# USB.net
KiCad netlist of a schematic drawn in Altium Designer
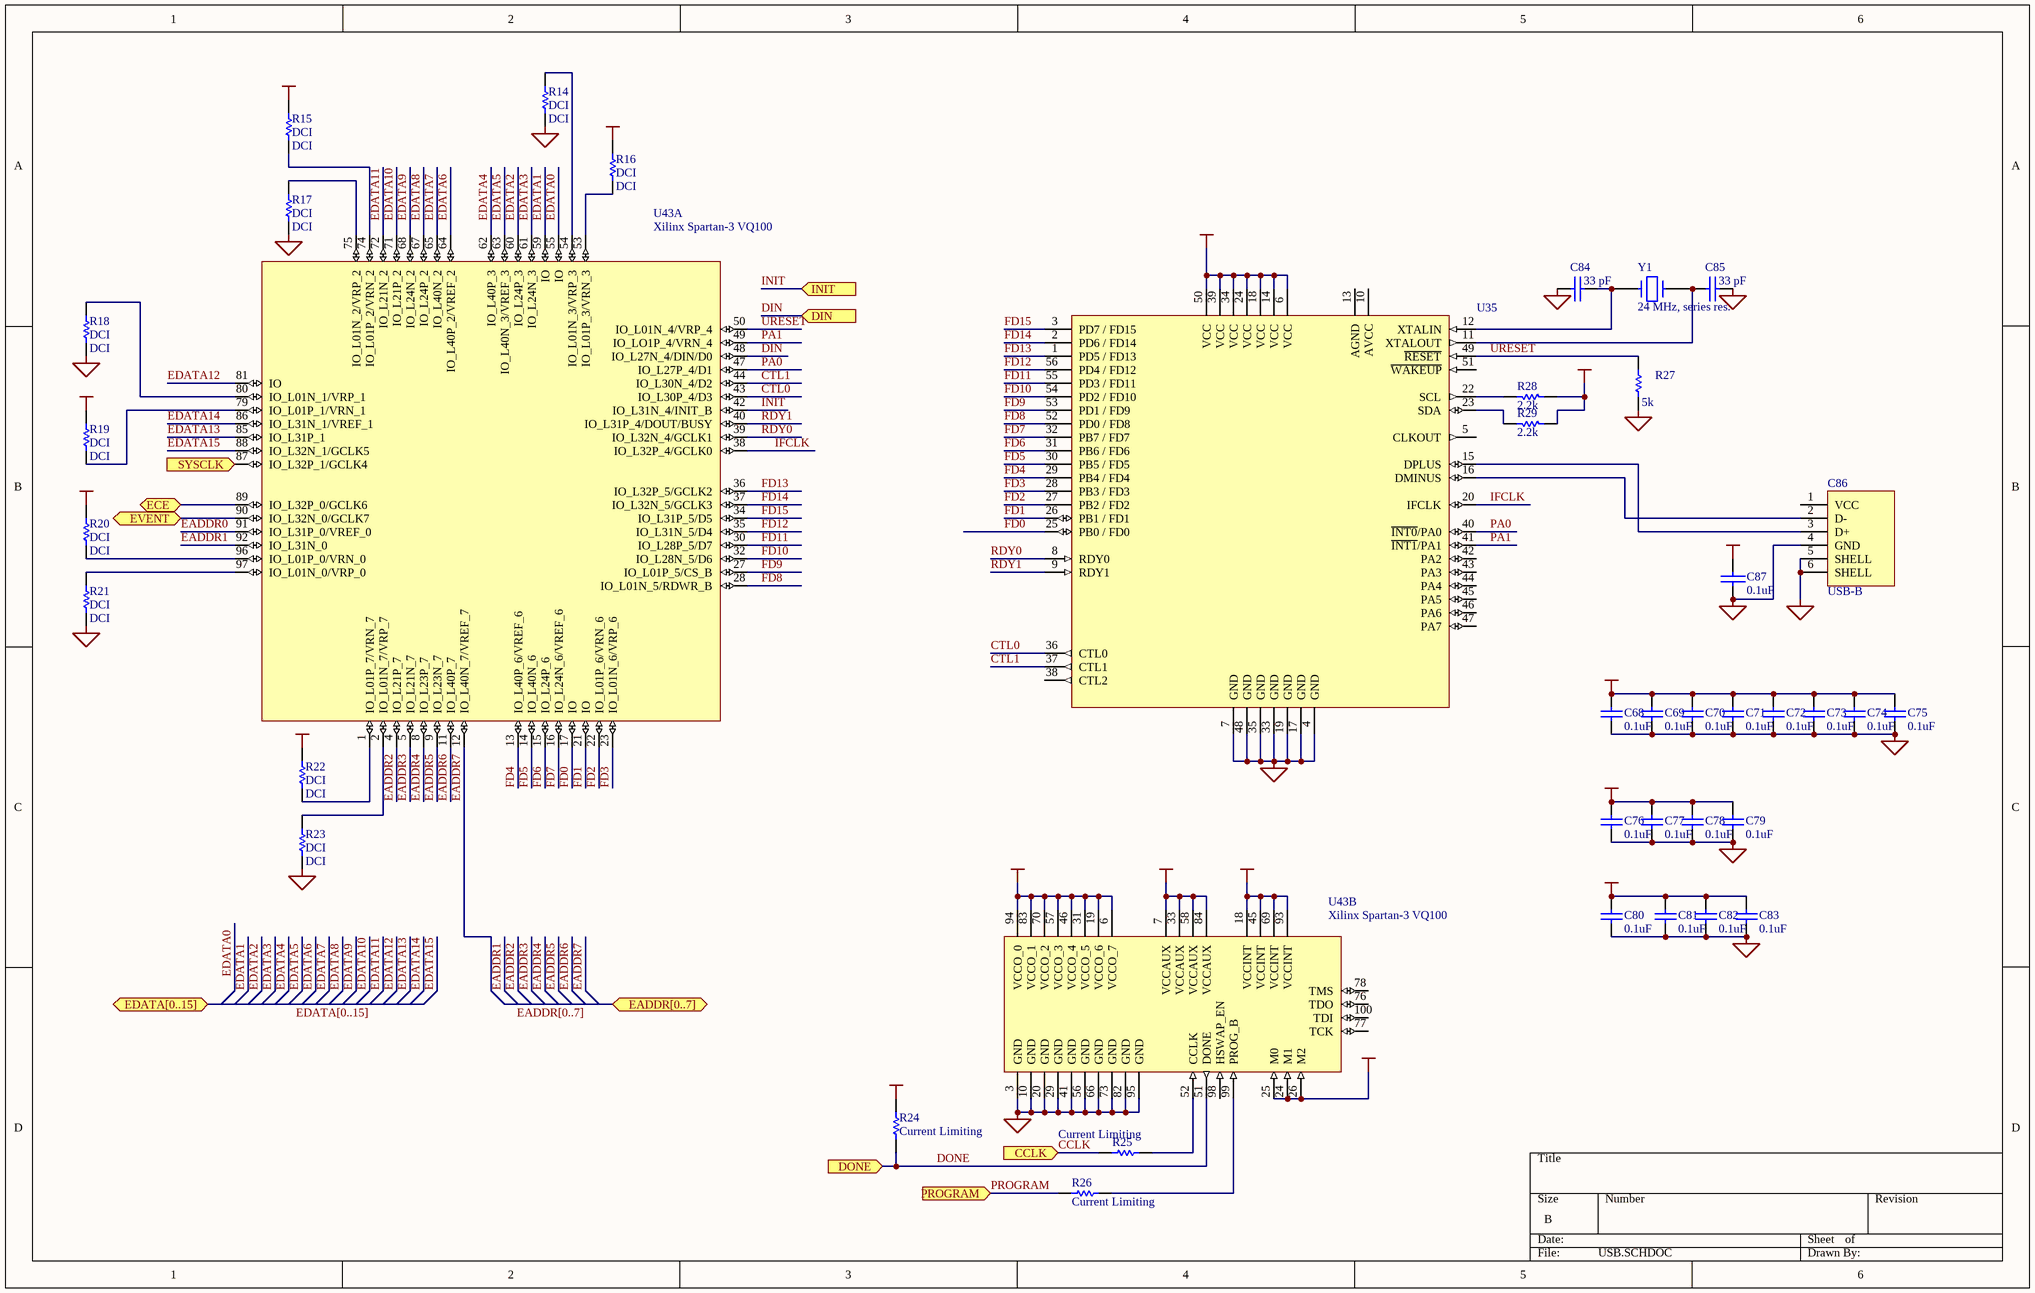
[diagram p0: USB.SCHDOC]

(export (version "E")
  (design (tool "Eeschema 10.0.6"))
  (components
    (comp (ref "C68")
      (value "Cap")
      (footprint "CC1608-0603")
      (description "Capacitor")
      (fields
        (field (name "MANUFACTURER") "Generic Components")
        (field (name "ALTIUM_VALUE") "0.1uF")
        (field (name "PUBLISHER") "Altium Limited")
      )
      (libsource (lib "Miscellaneous Devices") (part "Cap"))
    )
    (comp (ref "C69")
      (value "Cap")
      (footprint "CC1608-0603")
      (description "Capacitor")
      (fields
        (field (name "MANUFACTURER") "Generic Components")
        (field (name "ALTIUM_VALUE") "0.1uF")
        (field (name "PUBLISHER") "Altium Limited")
      )
      (libsource (lib "Miscellaneous Devices") (part "Cap"))
    )
    (comp (ref "C70")
      (value "Cap")
      (footprint "CC1608-0603")
      (description "Capacitor")
      (fields
        (field (name "MANUFACTURER") "Generic Components")
        (field (name "ALTIUM_VALUE") "0.1uF")
        (field (name "PUBLISHER") "Altium Limited")
      )
      (libsource (lib "Miscellaneous Devices") (part "Cap"))
    )
    (comp (ref "C71")
      (value "Cap")
      (footprint "CC1608-0603")
      (description "Capacitor")
      (fields
        (field (name "MANUFACTURER") "Generic Components")
        (field (name "ALTIUM_VALUE") "0.1uF")
        (field (name "PUBLISHER") "Altium Limited")
      )
      (libsource (lib "Miscellaneous Devices") (part "Cap"))
    )
    (comp (ref "C72")
      (value "Cap")
      (footprint "CC1608-0603")
      (description "Capacitor")
      (fields
        (field (name "MANUFACTURER") "Generic Components")
        (field (name "ALTIUM_VALUE") "0.1uF")
        (field (name "PUBLISHER") "Altium Limited")
      )
      (libsource (lib "Miscellaneous Devices") (part "Cap"))
    )
    (comp (ref "C73")
      (value "Cap")
      (footprint "CC1608-0603")
      (description "Capacitor")
      (fields
        (field (name "MANUFACTURER") "Generic Components")
        (field (name "ALTIUM_VALUE") "0.1uF")
        (field (name "PUBLISHER") "Altium Limited")
      )
      (libsource (lib "Miscellaneous Devices") (part "Cap"))
    )
    (comp (ref "C74")
      (value "Cap")
      (footprint "CC1608-0603")
      (description "Capacitor")
      (fields
        (field (name "MANUFACTURER") "Generic Components")
        (field (name "ALTIUM_VALUE") "0.1uF")
        (field (name "PUBLISHER") "Altium Limited")
      )
      (libsource (lib "Miscellaneous Devices") (part "Cap"))
    )
    (comp (ref "C75")
      (value "Cap")
      (footprint "CC1608-0603")
      (description "Capacitor")
      (fields
        (field (name "MANUFACTURER") "Generic Components")
        (field (name "ALTIUM_VALUE") "0.1uF")
        (field (name "PUBLISHER") "Altium Limited")
      )
      (libsource (lib "Miscellaneous Devices") (part "Cap"))
    )
    (comp (ref "C76")
      (value "Cap")
      (footprint "CC1608-0603")
      (description "Capacitor")
      (fields
        (field (name "MANUFACTURER") "Generic Components")
        (field (name "ALTIUM_VALUE") "0.1uF")
        (field (name "PUBLISHER") "Altium Limited")
      )
      (libsource (lib "Miscellaneous Devices") (part "Cap"))
    )
    (comp (ref "C77")
      (value "Cap")
      (footprint "CC1608-0603")
      (description "Capacitor")
      (fields
        (field (name "MANUFACTURER") "Generic Components")
        (field (name "ALTIUM_VALUE") "0.1uF")
        (field (name "PUBLISHER") "Altium Limited")
      )
      (libsource (lib "Miscellaneous Devices") (part "Cap"))
    )
    (comp (ref "C78")
      (value "Cap")
      (footprint "CC1608-0603")
      (description "Capacitor")
      (fields
        (field (name "MANUFACTURER") "Generic Components")
        (field (name "ALTIUM_VALUE") "0.1uF")
        (field (name "PUBLISHER") "Altium Limited")
      )
      (libsource (lib "Miscellaneous Devices") (part "Cap"))
    )
    (comp (ref "C79")
      (value "Cap")
      (footprint "CC1608-0603")
      (description "Capacitor")
      (fields
        (field (name "MANUFACTURER") "Generic Components")
        (field (name "ALTIUM_VALUE") "0.1uF")
        (field (name "PUBLISHER") "Altium Limited")
      )
      (libsource (lib "Miscellaneous Devices") (part "Cap"))
    )
    (comp (ref "C80")
      (value "Cap")
      (footprint "CC1608-0603")
      (description "Capacitor")
      (fields
        (field (name "MANUFACTURER") "Generic Components")
        (field (name "ALTIUM_VALUE") "0.1uF")
        (field (name "PUBLISHER") "Altium Limited")
      )
      (libsource (lib "Miscellaneous Devices") (part "Cap"))
    )
    (comp (ref "C81")
      (value "Cap")
      (footprint "CC1608-0603")
      (description "Capacitor")
      (fields
        (field (name "MANUFACTURER") "Generic Components")
        (field (name "ALTIUM_VALUE") "0.1uF")
        (field (name "PUBLISHER") "Altium Limited")
      )
      (libsource (lib "Miscellaneous Devices") (part "Cap"))
    )
    (comp (ref "C82")
      (value "Cap")
      (footprint "CC1608-0603")
      (description "Capacitor")
      (fields
        (field (name "MANUFACTURER") "Generic Components")
        (field (name "ALTIUM_VALUE") "0.1uF")
        (field (name "PUBLISHER") "Altium Limited")
      )
      (libsource (lib "Miscellaneous Devices") (part "Cap"))
    )
    (comp (ref "C83")
      (value "Cap")
      (footprint "CC1608-0603")
      (description "Capacitor")
      (fields
        (field (name "MANUFACTURER") "Generic Components")
        (field (name "ALTIUM_VALUE") "0.1uF")
        (field (name "PUBLISHER") "Altium Limited")
      )
      (libsource (lib "Miscellaneous Devices") (part "Cap"))
    )
    (comp (ref "C84")
      (value "33 pF")
      (footprint "CC1608-0603")
      (description "Capacitor")
      (libsource (lib "*") (part "CAP"))
    )
    (comp (ref "C85")
      (value "33 pF")
      (footprint "CC1608-0603")
      (description "Capacitor")
      (libsource (lib "*") (part "CAP"))
    )
    (comp (ref "C86") (value "USB-B") (footprint "USB-B") (libsource (lib "*") (part "USB-B")))
    (comp (ref "C87")
      (value "0.1uF")
      (footprint "CC1608-0603")
      (description "Capacitor")
      (libsource (lib "*") (part "CAP"))
    )
    (comp (ref "R14")
      (value "DCI")
      (footprint "CC1608-0603")
      (description "Resistor")
      (fields
        (field (name "MANUFACTURER") "Generic Components")
        (field (name "ALTIUM_VALUE") "DCI")
        (field (name "PUBLISHER") "Altium Limited")
      )
      (libsource (lib "Miscellaneous Devices") (part "Res1"))
    )
    (comp (ref "R15")
      (value "DCI")
      (footprint "CC1608-0603")
      (description "Resistor")
      (fields
        (field (name "MANUFACTURER") "Generic Components")
        (field (name "ALTIUM_VALUE") "DCI")
        (field (name "PUBLISHER") "Altium Limited")
      )
      (libsource (lib "Miscellaneous Devices") (part "Res1"))
    )
    (comp (ref "R16")
      (value "DCI")
      (footprint "CC1608-0603")
      (description "Resistor")
      (fields
        (field (name "MANUFACTURER") "Generic Components")
        (field (name "ALTIUM_VALUE") "DCI")
        (field (name "PUBLISHER") "Altium Limited")
      )
      (libsource (lib "Miscellaneous Devices") (part "Res1"))
    )
    (comp (ref "R17")
      (value "DCI")
      (footprint "CC1608-0603")
      (description "Resistor")
      (fields
        (field (name "MANUFACTURER") "Generic Components")
        (field (name "ALTIUM_VALUE") "DCI")
        (field (name "PUBLISHER") "Altium Limited")
      )
      (libsource (lib "Miscellaneous Devices") (part "Res1"))
    )
    (comp (ref "R18")
      (value "DCI")
      (footprint "CC1608-0603")
      (description "Resistor")
      (fields
        (field (name "MANUFACTURER") "Generic Components")
        (field (name "ALTIUM_VALUE") "DCI")
        (field (name "PUBLISHER") "Altium Limited")
      )
      (libsource (lib "Miscellaneous Devices") (part "Res1"))
    )
    (comp (ref "R19")
      (value "DCI")
      (footprint "CC1608-0603")
      (description "Resistor")
      (fields
        (field (name "MANUFACTURER") "Generic Components")
        (field (name "ALTIUM_VALUE") "DCI")
        (field (name "PUBLISHER") "Altium Limited")
      )
      (libsource (lib "Miscellaneous Devices") (part "Res1"))
    )
    (comp (ref "R20")
      (value "DCI")
      (footprint "CC1608-0603")
      (description "Resistor")
      (fields
        (field (name "MANUFACTURER") "Generic Components")
        (field (name "ALTIUM_VALUE") "DCI")
        (field (name "PUBLISHER") "Altium Limited")
      )
      (libsource (lib "Miscellaneous Devices") (part "Res1"))
    )
    (comp (ref "R21")
      (value "DCI")
      (footprint "CC1608-0603")
      (description "Resistor")
      (fields
        (field (name "MANUFACTURER") "Generic Components")
        (field (name "ALTIUM_VALUE") "DCI")
        (field (name "PUBLISHER") "Altium Limited")
      )
      (libsource (lib "Miscellaneous Devices") (part "Res1"))
    )
    (comp (ref "R22")
      (value "DCI")
      (footprint "CC1608-0603")
      (description "Resistor")
      (fields
        (field (name "MANUFACTURER") "Generic Components")
        (field (name "ALTIUM_VALUE") "DCI")
        (field (name "PUBLISHER") "Altium Limited")
      )
      (libsource (lib "Miscellaneous Devices") (part "Res1"))
    )
    (comp (ref "R23")
      (value "DCI")
      (footprint "CC1608-0603")
      (description "Resistor")
      (fields
        (field (name "MANUFACTURER") "Generic Components")
        (field (name "ALTIUM_VALUE") "DCI")
        (field (name "PUBLISHER") "Altium Limited")
      )
      (libsource (lib "Miscellaneous Devices") (part "Res1"))
    )
    (comp (ref "R24")
      (value "Current Limiting")
      (footprint "CC1608-0603")
      (description "Resistor")
      (fields (field (name "MANUFACTURER") "Generic Components") (field (name "PUBLISHER") "Altium Limited"))
      (libsource (lib "Miscellaneous Devices") (part "Res1"))
    )
    (comp (ref "R25")
      (value "Current Limiting")
      (footprint "CC1608-0603")
      (description "Resistor")
      (fields (field (name "MANUFACTURER") "Generic Components") (field (name "PUBLISHER") "Altium Limited"))
      (libsource (lib "Miscellaneous Devices") (part "Res1"))
    )
    (comp (ref "R26")
      (value "Current Limiting")
      (footprint "CC1608-0603")
      (description "Resistor")
      (fields (field (name "MANUFACTURER") "Generic Components") (field (name "PUBLISHER") "Altium Limited"))
      (libsource (lib "Miscellaneous Devices") (part "Res1"))
    )
    (comp (ref "R27")
      (value "Res1")
      (footprint "CC3216-1206")
      (description "Resistor")
      (fields
        (field (name "MANUFACTURER") "Generic Components")
        (field (name "ALTIUM_VALUE") "5k")
        (field (name "PUBLISHER") "Altium Limited")
      )
      (libsource (lib "Miscellaneous Devices") (part "Res1"))
    )
    (comp (ref "R28")
      (value "Res1")
      (footprint "CC3216-1206")
      (description "Resistor")
      (fields
        (field (name "MANUFACTURER") "Generic Components")
        (field (name "ALTIUM_VALUE") "2.2k")
        (field (name "PUBLISHER") "Altium Limited")
      )
      (libsource (lib "Miscellaneous Devices") (part "Res1"))
    )
    (comp (ref "R29")
      (value "Res1")
      (footprint "CC3216-1206")
      (description "Resistor")
      (fields
        (field (name "MANUFACTURER") "Generic Components")
        (field (name "ALTIUM_VALUE") "2.2k")
        (field (name "PUBLISHER") "Altium Limited")
      )
      (libsource (lib "Miscellaneous Devices") (part "Res1"))
    )
    (comp (ref "U35")
      (value "~")
      (footprint "SOP56FX2")
      (description "Cypress EZ-USB FX2")
      (libsource (lib "My devices") (part "CY7C68013-56"))
    )
    (comp (ref "U43")
      (value "Xilinx Spartan-3 VQ100")
      (footprint "F-QFP14X14-G100/N")
      (libsource (lib "My devices") (part "XC3S50-VQ100"))
    )
    (comp (ref "Y1")
      (value "24 MHz, series res.")
      (footprint "ECX-3S")
      (description "Crystal")
      (libsource (lib "*") (part "CRYSTAL"))
    )
  )
  (nets
    (net (code "1") (name "+1.2VCCUSB") (class "Default")
      (node (ref "C76") (pin "1") (pinfunction "1_1") (pintype "passive"))
      (node (ref "C77") (pin "1") (pinfunction "1_1") (pintype "passive"))
      (node (ref "C78") (pin "1") (pinfunction "1_1") (pintype "passive"))
      (node (ref "C79") (pin "1") (pinfunction "1_1") (pintype "passive"))
      (node (ref "U43") (pin "18") (pinfunction "VCCINT_18") (pintype "power_in"))
      (node (ref "U43") (pin "45") (pinfunction "VCCINT_45") (pintype "power_in"))
      (node (ref "U43") (pin "69") (pinfunction "VCCINT_69") (pintype "power_in"))
      (node (ref "U43") (pin "93") (pinfunction "VCCINT_93") (pintype "power_in"))
    )
    (net (code "2") (name "+2.5VCC") (class "Default")
      (node (ref "C80") (pin "1") (pinfunction "1_1") (pintype "passive"))
      (node (ref "C81") (pin "1") (pinfunction "1_1") (pintype "passive"))
      (node (ref "C82") (pin "1") (pinfunction "1_1") (pintype "passive"))
      (node (ref "C83") (pin "1") (pinfunction "1_1") (pintype "passive"))
      (node (ref "U43") (pin "33") (pinfunction "VCCAUX_33") (pintype "power_in"))
      (node (ref "U43") (pin "58") (pinfunction "VCCAUX_58") (pintype "power_in"))
      (node (ref "U43") (pin "7") (pinfunction "VCCAUX_7") (pintype "power_in"))
      (node (ref "U43") (pin "84") (pinfunction "VCCAUX_84") (pintype "power_in"))
    )
    (net (code "3") (name "/CCLK") (class "Default")
      (node (ref "R25") (pin "1") (pinfunction "1_1") (pintype "passive"))
    )
    (net (code "4") (name "/CTL0") (class "Default")
      (node (ref "U35") (pin "36") (pinfunction "CTL0_36") (pintype "output"))
      (node (ref "U43") (pin "43") (pinfunction "IO_L30P_4/D3_43") (pintype "bidirectional"))
    )
    (net (code "5") (name "/CTL1") (class "Default")
      (node (ref "U35") (pin "37") (pinfunction "CTL1_37") (pintype "output"))
      (node (ref "U43") (pin "44") (pinfunction "IO_L30N_4/D2_44") (pintype "bidirectional"))
    )
    (net (code "6") (name "/DIN") (class "Default")
      (node (ref "U43") (pin "48") (pinfunction "IO_L27N_4/DIN/D0_48") (pintype "bidirectional"))
    )
    (net (code "7") (name "/DONE") (class "Default")
      (node (ref "R24") (pin "1") (pinfunction "1_1") (pintype "passive"))
      (node (ref "U43") (pin "51") (pinfunction "DONE_51") (pintype "output"))
    )
    (net (code "8") (name "/EADDR0") (class "Default")
      (node (ref "U43") (pin "91") (pinfunction "IO_L31P_0/VREF_0_91") (pintype "bidirectional"))
    )
    (net (code "9") (name "/EADDR1") (class "Default")
      (node (ref "U43") (pin "92") (pinfunction "IO_L31N_0_92") (pintype "bidirectional"))
    )
    (net (code "10") (name "/EADDR2") (class "Default")
      (node (ref "U43") (pin "4") (pinfunction "IO_L21P_7_4") (pintype "bidirectional"))
    )
    (net (code "11") (name "/EADDR3") (class "Default")
      (node (ref "U43") (pin "5") (pinfunction "IO_L21N_7_5") (pintype "bidirectional"))
    )
    (net (code "12") (name "/EADDR4") (class "Default")
      (node (ref "U43") (pin "8") (pinfunction "IO_L23P_7_8") (pintype "bidirectional"))
    )
    (net (code "13") (name "/EADDR5") (class "Default")
      (node (ref "U43") (pin "9") (pinfunction "IO_L23N_7_9") (pintype "bidirectional"))
    )
    (net (code "14") (name "/EADDR6") (class "Default")
      (node (ref "U43") (pin "11") (pinfunction "IO_L40P_7_11") (pintype "bidirectional"))
    )
    (net (code "15") (name "/EADDR7") (class "Default")
      (node (ref "U43") (pin "12") (pinfunction "IO_L40N_7/VREF_7_12") (pintype "bidirectional"))
    )
    (net (code "17") (name "/ECE") (class "Default")
      (node (ref "U43") (pin "89") (pinfunction "IO_L32P_0/GCLK6_89") (pintype "bidirectional"))
    )
    (net (code "18") (name "/EDATA0") (class "Default")
      (node (ref "U43") (pin "55") (pinfunction "IO_55") (pintype "bidirectional"))
    )
    (net (code "19") (name "/EDATA1") (class "Default")
      (node (ref "U43") (pin "59") (pinfunction "IO_59") (pintype "bidirectional"))
    )
    (net (code "20") (name "/EDATA2") (class "Default")
      (node (ref "U43") (pin "60") (pinfunction "IO_L24P_3_60") (pintype "bidirectional"))
    )
    (net (code "21") (name "/EDATA3") (class "Default")
      (node (ref "U43") (pin "61") (pinfunction "IO_L24N_3_61") (pintype "bidirectional"))
    )
    (net (code "22") (name "/EDATA4") (class "Default")
      (node (ref "U43") (pin "62") (pinfunction "IO_L40P_3_62") (pintype "bidirectional"))
    )
    (net (code "23") (name "/EDATA5") (class "Default")
      (node (ref "U43") (pin "63") (pinfunction "IO_L40N_3/VREF_3_63") (pintype "bidirectional"))
    )
    (net (code "24") (name "/EDATA6") (class "Default")
      (node (ref "U43") (pin "64") (pinfunction "IO_L40P_2/VREF_2_64") (pintype "bidirectional"))
    )
    (net (code "25") (name "/EDATA7") (class "Default")
      (node (ref "U43") (pin "65") (pinfunction "IO_L40N_2_65") (pintype "bidirectional"))
    )
    (net (code "26") (name "/EDATA8") (class "Default")
      (node (ref "U43") (pin "67") (pinfunction "IO_L24P_2_67") (pintype "bidirectional"))
    )
    (net (code "27") (name "/EDATA9") (class "Default")
      (node (ref "U43") (pin "68") (pinfunction "IO_L24N_2_68") (pintype "bidirectional"))
    )
    (net (code "28") (name "/EDATA10") (class "Default")
      (node (ref "U43") (pin "71") (pinfunction "IO_L21P_2_71") (pintype "bidirectional"))
    )
    (net (code "29") (name "/EDATA11") (class "Default")
      (node (ref "U43") (pin "72") (pinfunction "IO_L21N_2_72") (pintype "bidirectional"))
    )
    (net (code "30") (name "/EDATA12") (class "Default")
      (node (ref "U43") (pin "81") (pinfunction "IO_81") (pintype "bidirectional"))
    )
    (net (code "31") (name "/EDATA13") (class "Default")
      (node (ref "U43") (pin "85") (pinfunction "IO_L31P_1_85") (pintype "bidirectional"))
    )
    (net (code "32") (name "/EDATA14") (class "Default")
      (node (ref "U43") (pin "86") (pinfunction "IO_L31N_1/VREF_1_86") (pintype "bidirectional"))
    )
    (net (code "33") (name "/EDATA15") (class "Default")
      (node (ref "U43") (pin "88") (pinfunction "IO_L32N_1/GCLK5_88") (pintype "bidirectional"))
    )
    (net (code "35") (name "/EVENT") (class "Default")
      (node (ref "U43") (pin "90") (pinfunction "IO_L32N_0/GCLK7_90") (pintype "bidirectional"))
    )
    (net (code "36") (name "/FD0") (class "Default")
      (node (ref "U35") (pin "25") (pinfunction "PB0_/_FD0_25") (pintype "bidirectional"))
      (node (ref "U43") (pin "17") (pinfunction "IO_17") (pintype "bidirectional"))
    )
    (net (code "37") (name "/FD1") (class "Default")
      (node (ref "U35") (pin "26") (pinfunction "PB1_/_FD1_26") (pintype "bidirectional"))
      (node (ref "U43") (pin "21") (pinfunction "IO_21") (pintype "bidirectional"))
    )
    (net (code "38") (name "/FD2") (class "Default")
      (node (ref "U35") (pin "27") (pinfunction "PB2_/_FD2_27") (pintype "passive"))
      (node (ref "U43") (pin "22") (pinfunction "IO_L01P_6/VRN_6_22") (pintype "bidirectional"))
    )
    (net (code "39") (name "/FD3") (class "Default")
      (node (ref "U35") (pin "28") (pinfunction "PB3_/_FD3_28") (pintype "passive"))
      (node (ref "U43") (pin "23") (pinfunction "IO_L01N_6/VRP_6_23") (pintype "bidirectional"))
    )
    (net (code "40") (name "/FD4") (class "Default")
      (node (ref "U35") (pin "29") (pinfunction "PB4_/_FD4_29") (pintype "passive"))
      (node (ref "U43") (pin "13") (pinfunction "IO_L40P_6/VREF_6_13") (pintype "bidirectional"))
    )
    (net (code "41") (name "/FD5") (class "Default")
      (node (ref "U35") (pin "30") (pinfunction "PB5_/_FD5_30") (pintype "passive"))
      (node (ref "U43") (pin "14") (pinfunction "IO_L40N_6_14") (pintype "bidirectional"))
    )
    (net (code "42") (name "/FD6") (class "Default")
      (node (ref "U35") (pin "31") (pinfunction "PB6_/_FD6_31") (pintype "passive"))
      (node (ref "U43") (pin "15") (pinfunction "IO_L24P_6_15") (pintype "bidirectional"))
    )
    (net (code "43") (name "/FD7") (class "Default")
      (node (ref "U35") (pin "32") (pinfunction "PB7_/_FD7_32") (pintype "passive"))
      (node (ref "U43") (pin "16") (pinfunction "IO_L24N_6/VREF_6_16") (pintype "bidirectional"))
    )
    (net (code "44") (name "/FD8") (class "Default")
      (node (ref "U35") (pin "52") (pinfunction "PD0_/_FD8_52") (pintype "passive"))
      (node (ref "U43") (pin "28") (pinfunction "IO_L01N_5/RDWR_B_28") (pintype "bidirectional"))
    )
    (net (code "45") (name "/FD9") (class "Default")
      (node (ref "U35") (pin "53") (pinfunction "PD1_/_FD9_53") (pintype "passive"))
      (node (ref "U43") (pin "27") (pinfunction "IO_L01P_5/CS_B_27") (pintype "bidirectional"))
    )
    (net (code "46") (name "/FD10") (class "Default")
      (node (ref "U35") (pin "54") (pinfunction "PD2_/_FD10_54") (pintype "passive"))
      (node (ref "U43") (pin "32") (pinfunction "IO_L28N_5/D6_32") (pintype "bidirectional"))
    )
    (net (code "47") (name "/FD11") (class "Default")
      (node (ref "U35") (pin "55") (pinfunction "PD3_/_FD11_55") (pintype "passive"))
      (node (ref "U43") (pin "30") (pinfunction "IO_L28P_5/D7_30") (pintype "bidirectional"))
    )
    (net (code "48") (name "/FD12") (class "Default")
      (node (ref "U35") (pin "56") (pinfunction "PD4_/_FD12_56") (pintype "passive"))
      (node (ref "U43") (pin "35") (pinfunction "IO_L31N_5/D4_35") (pintype "bidirectional"))
    )
    (net (code "49") (name "/FD13") (class "Default")
      (node (ref "U35") (pin "1") (pinfunction "PD5_/_FD13_1") (pintype "passive"))
      (node (ref "U43") (pin "36") (pinfunction "IO_L32P_5/GCLK2_36") (pintype "bidirectional"))
    )
    (net (code "50") (name "/FD14") (class "Default")
      (node (ref "U35") (pin "2") (pinfunction "PD6_/_FD14_2") (pintype "passive"))
      (node (ref "U43") (pin "37") (pinfunction "IO_L32N_5/GCLK3_37") (pintype "bidirectional"))
    )
    (net (code "51") (name "/FD15") (class "Default")
      (node (ref "U35") (pin "3") (pinfunction "PD7_/_FD15_3") (pintype "passive"))
      (node (ref "U43") (pin "34") (pinfunction "IO_L31P_5/D5_34") (pintype "bidirectional"))
    )
    (net (code "52") (name "/IFCLK") (class "Default")
      (node (ref "U35") (pin "20") (pinfunction "IFCLK_20") (pintype "bidirectional"))
      (node (ref "U43") (pin "38") (pinfunction "IO_L32P_4/GCLK0_38") (pintype "bidirectional"))
    )
    (net (code "53") (name "/INIT") (class "Default")
      (node (ref "U43") (pin "42") (pinfunction "IO_L31N_4/INIT_B_42") (pintype "bidirectional"))
    )
    (net (code "54") (name "/PA0") (class "Default")
      (node (ref "U35") (pin "40") (pinfunction "~{INT0}/PA0_40") (pintype "bidirectional"))
      (node (ref "U43") (pin "47") (pinfunction "IO_L27P_4/D1_47") (pintype "bidirectional"))
    )
    (net (code "55") (name "/PA1") (class "Default")
      (node (ref "U35") (pin "41") (pinfunction "~{INT1}/PA1_41") (pintype "bidirectional"))
      (node (ref "U43") (pin "49") (pinfunction "IO_LO1P_4/VRN_4_49") (pintype "bidirectional"))
    )
    (net (code "56") (name "/PROGRAM") (class "Default")
      (node (ref "R26") (pin "1") (pinfunction "1_1") (pintype "passive"))
    )
    (net (code "57") (name "/RDY0") (class "Default")
      (node (ref "U35") (pin "8") (pinfunction "RDY0_8") (pintype "input"))
      (node (ref "U43") (pin "39") (pinfunction "IO_L32N_4/GCLK1_39") (pintype "bidirectional"))
    )
    (net (code "58") (name "/RDY1") (class "Default")
      (node (ref "U35") (pin "9") (pinfunction "RDY1_9") (pintype "input"))
      (node (ref "U43") (pin "40") (pinfunction "IO_L31P_4/DOUT/BUSY_40") (pintype "bidirectional"))
    )
    (net (code "59") (name "/SYSCLK") (class "Default")
      (node (ref "U43") (pin "87") (pinfunction "IO_L32P_1/GCLK4_87") (pintype "bidirectional"))
    )
    (net (code "60") (name "/URESET") (class "Default")
      (node (ref "R27") (pin "2") (pinfunction "2_2") (pintype "passive"))
      (node (ref "U35") (pin "49") (pinfunction "~{RESET}_49") (pintype "input"))
      (node (ref "U43") (pin "50") (pinfunction "IO_L01N_4/VRP_4_50") (pintype "bidirectional"))
    )
    (net (code "61") (name "GND") (class "Default")
      (node (ref "C68") (pin "2") (pinfunction "2_2") (pintype "passive"))
      (node (ref "C69") (pin "2") (pinfunction "2_2") (pintype "passive"))
      (node (ref "C70") (pin "2") (pinfunction "2_2") (pintype "passive"))
      (node (ref "C71") (pin "2") (pinfunction "2_2") (pintype "passive"))
      (node (ref "C72") (pin "2") (pinfunction "2_2") (pintype "passive"))
      (node (ref "C73") (pin "2") (pinfunction "2_2") (pintype "passive"))
      (node (ref "C74") (pin "2") (pinfunction "2_2") (pintype "passive"))
      (node (ref "C75") (pin "2") (pinfunction "2_2") (pintype "passive"))
      (node (ref "C76") (pin "2") (pinfunction "2_2") (pintype "passive"))
      (node (ref "C77") (pin "2") (pinfunction "2_2") (pintype "passive"))
      (node (ref "C78") (pin "2") (pinfunction "2_2") (pintype "passive"))
      (node (ref "C79") (pin "2") (pinfunction "2_2") (pintype "passive"))
      (node (ref "C80") (pin "2") (pinfunction "2_2") (pintype "passive"))
      (node (ref "C81") (pin "2") (pinfunction "2_2") (pintype "passive"))
      (node (ref "C82") (pin "2") (pinfunction "2_2") (pintype "passive"))
      (node (ref "C83") (pin "2") (pinfunction "2_2") (pintype "passive"))
      (node (ref "C84") (pin "2") (pinfunction "2_2") (pintype "passive"))
      (node (ref "C85") (pin "1") (pinfunction "1_1") (pintype "passive"))
      (node (ref "C86") (pin "4") (pinfunction "GND_4") (pintype "passive"))
      (node (ref "C86") (pin "5") (pinfunction "SHELL_5") (pintype "passive"))
      (node (ref "C86") (pin "6") (pinfunction "SHELL_6") (pintype "passive"))
      (node (ref "C87") (pin "2") (pinfunction "2_2") (pintype "passive"))
      (node (ref "R14") (pin "1") (pinfunction "1_1") (pintype "passive"))
      (node (ref "R17") (pin "1") (pinfunction "1_1") (pintype "passive"))
      (node (ref "R18") (pin "1") (pinfunction "1_1") (pintype "passive"))
      (node (ref "R21") (pin "1") (pinfunction "1_1") (pintype "passive"))
      (node (ref "R23") (pin "1") (pinfunction "1_1") (pintype "passive"))
      (node (ref "R27") (pin "1") (pinfunction "1_1") (pintype "passive"))
      (node (ref "U35") (pin "17") (pinfunction "GND_17") (pintype "power_in"))
      (node (ref "U35") (pin "19") (pinfunction "GND_19") (pintype "power_in"))
      (node (ref "U35") (pin "33") (pinfunction "GND_33") (pintype "power_in"))
      (node (ref "U35") (pin "35") (pinfunction "GND_35") (pintype "power_in"))
      (node (ref "U35") (pin "4") (pinfunction "GND_4") (pintype "power_in"))
      (node (ref "U35") (pin "48") (pinfunction "GND_48") (pintype "power_in"))
      (node (ref "U35") (pin "7") (pinfunction "GND_7") (pintype "power_in"))
      (node (ref "U43") (pin "10") (pinfunction "GND_10") (pintype "power_in"))
      (node (ref "U43") (pin "20") (pinfunction "GND_20") (pintype "power_in"))
      (node (ref "U43") (pin "29") (pinfunction "GND_29") (pintype "power_in"))
      (node (ref "U43") (pin "3") (pinfunction "GND_3") (pintype "power_in"))
      (node (ref "U43") (pin "41") (pinfunction "GND_41") (pintype "power_in"))
      (node (ref "U43") (pin "56") (pinfunction "GND_56") (pintype "power_in"))
      (node (ref "U43") (pin "66") (pinfunction "GND_66") (pintype "power_in"))
      (node (ref "U43") (pin "73") (pinfunction "GND_73") (pintype "power_in"))
      (node (ref "U43") (pin "82") (pinfunction "GND_82") (pintype "power_in"))
      (node (ref "U43") (pin "95") (pinfunction "GND_95") (pintype "power_in"))
    )
    (net (code "62") (name "Net-(C86-D+)") (class "Default")
      (node (ref "C86") (pin "3") (pinfunction "D+_3") (pintype "passive"))
      (node (ref "U35") (pin "15") (pinfunction "DPLUS_15") (pintype "bidirectional"))
    )
    (net (code "63") (name "Net-(C86-D-)") (class "Default")
      (node (ref "C86") (pin "2") (pinfunction "D-_2") (pintype "passive"))
      (node (ref "U35") (pin "16") (pinfunction "DMINUS_16") (pintype "bidirectional"))
    )
    (net (code "64") (name "Net-(U35-SCL)") (class "Default")
      (node (ref "R28") (pin "2") (pinfunction "2_2") (pintype "passive"))
      (node (ref "U35") (pin "22") (pinfunction "SCL_22") (pintype "output"))
    )
    (net (code "65") (name "Net-(U35-SDA)") (class "Default")
      (node (ref "R29") (pin "2") (pinfunction "2_2") (pintype "passive"))
      (node (ref "U35") (pin "23") (pinfunction "SDA_23") (pintype "bidirectional"))
    )
    (net (code "66") (name "Net-(U35-XTALIN)") (class "Default")
      (node (ref "C84") (pin "1") (pinfunction "1_1") (pintype "passive"))
      (node (ref "U35") (pin "12") (pinfunction "XTALIN_12") (pintype "input"))
      (node (ref "Y1") (pin "1") (pinfunction "1_1") (pintype "passive"))
    )
    (net (code "67") (name "Net-(U35-XTALOUT)") (class "Default")
      (node (ref "C85") (pin "2") (pinfunction "2_2") (pintype "passive"))
      (node (ref "U35") (pin "11") (pinfunction "XTALOUT_11") (pintype "output"))
      (node (ref "Y1") (pin "2") (pinfunction "2_2") (pintype "passive"))
    )
    (net (code "68") (name "Net-(U43A-IO_L01N_0{slash}VRP_0)") (class "Default")
      (node (ref "R21") (pin "2") (pinfunction "2_2") (pintype "passive"))
      (node (ref "U43") (pin "97") (pinfunction "IO_L01N_0/VRP_0_97") (pintype "bidirectional"))
    )
    (net (code "69") (name "Net-(U43A-IO_L01N_1{slash}VRP_1)") (class "Default")
      (node (ref "R18") (pin "2") (pinfunction "2_2") (pintype "passive"))
      (node (ref "U43") (pin "80") (pinfunction "IO_L01N_1/VRP_1_80") (pintype "bidirectional"))
    )
    (net (code "70") (name "Net-(U43A-IO_L01N_2{slash}VRP_2)") (class "Default")
      (node (ref "R17") (pin "2") (pinfunction "2_2") (pintype "passive"))
      (node (ref "U43") (pin "75") (pinfunction "IO_L01N_2/VRP_2_75") (pintype "bidirectional"))
    )
    (net (code "71") (name "Net-(U43A-IO_L01N_3{slash}VRP_3)") (class "Default")
      (node (ref "R14") (pin "2") (pinfunction "2_2") (pintype "passive"))
      (node (ref "U43") (pin "54") (pinfunction "IO_L01N_3/VRP_3_54") (pintype "bidirectional"))
    )
    (net (code "72") (name "Net-(U43A-IO_L01N_7{slash}VRP_7)") (class "Default")
      (node (ref "R23") (pin "2") (pinfunction "2_2") (pintype "passive"))
      (node (ref "U43") (pin "2") (pinfunction "IO_L01N_7/VRP_7_2") (pintype "bidirectional"))
    )
    (net (code "73") (name "Net-(U43A-IO_L01P_0{slash}VRN_0)") (class "Default")
      (node (ref "R20") (pin "1") (pinfunction "1_1") (pintype "passive"))
      (node (ref "U43") (pin "96") (pinfunction "IO_L01P_0/VRN_0_96") (pintype "bidirectional"))
    )
    (net (code "74") (name "Net-(U43A-IO_L01P_1{slash}VRN_1)") (class "Default")
      (node (ref "R19") (pin "1") (pinfunction "1_1") (pintype "passive"))
      (node (ref "U43") (pin "79") (pinfunction "IO_L01P_1/VRN_1_79") (pintype "bidirectional"))
    )
    (net (code "75") (name "Net-(U43A-IO_L01P_2{slash}VRN_2)") (class "Default")
      (node (ref "R15") (pin "1") (pinfunction "1_1") (pintype "passive"))
      (node (ref "U43") (pin "74") (pinfunction "IO_L01P_2/VRN_2_74") (pintype "bidirectional"))
    )
    (net (code "76") (name "Net-(U43A-IO_L01P_3{slash}VRN_3)") (class "Default")
      (node (ref "R16") (pin "1") (pinfunction "1_1") (pintype "passive"))
      (node (ref "U43") (pin "53") (pinfunction "IO_L01P_3/VRN_3_53") (pintype "bidirectional"))
    )
    (net (code "77") (name "Net-(U43A-IO_L01P_7{slash}VRN_7)") (class "Default")
      (node (ref "R22") (pin "1") (pinfunction "1_1") (pintype "passive"))
      (node (ref "U43") (pin "1") (pinfunction "IO_L01P_7/VRN_7_1") (pintype "bidirectional"))
    )
    (net (code "78") (name "Net-(U43B-CCLK)") (class "Default")
      (node (ref "R25") (pin "2") (pinfunction "2_2") (pintype "passive"))
      (node (ref "U43") (pin "52") (pinfunction "CCLK_52") (pintype "input"))
    )
    (net (code "79") (name "Net-(U43B-PROG_B)") (class "Default")
      (node (ref "R26") (pin "2") (pinfunction "2_2") (pintype "passive"))
      (node (ref "U43") (pin "99") (pinfunction "PROG_B_99") (pintype "input"))
    )
    (net (code "80") (name "VCC") (class "Default")
      (node (ref "C68") (pin "1") (pinfunction "1_1") (pintype "passive"))
      (node (ref "C69") (pin "1") (pinfunction "1_1") (pintype "passive"))
      (node (ref "C70") (pin "1") (pinfunction "1_1") (pintype "passive"))
      (node (ref "C71") (pin "1") (pinfunction "1_1") (pintype "passive"))
      (node (ref "C72") (pin "1") (pinfunction "1_1") (pintype "passive"))
      (node (ref "C73") (pin "1") (pinfunction "1_1") (pintype "passive"))
      (node (ref "C74") (pin "1") (pinfunction "1_1") (pintype "passive"))
      (node (ref "C75") (pin "1") (pinfunction "1_1") (pintype "passive"))
      (node (ref "C87") (pin "1") (pinfunction "1_1") (pintype "passive"))
      (node (ref "R15") (pin "2") (pinfunction "2_2") (pintype "passive"))
      (node (ref "R16") (pin "2") (pinfunction "2_2") (pintype "passive"))
      (node (ref "R19") (pin "2") (pinfunction "2_2") (pintype "passive"))
      (node (ref "R20") (pin "2") (pinfunction "2_2") (pintype "passive"))
      (node (ref "R22") (pin "2") (pinfunction "2_2") (pintype "passive"))
      (node (ref "R24") (pin "2") (pinfunction "2_2") (pintype "passive"))
      (node (ref "R28") (pin "1") (pinfunction "1_1") (pintype "passive"))
      (node (ref "R29") (pin "1") (pinfunction "1_1") (pintype "passive"))
      (node (ref "U35") (pin "14") (pinfunction "VCC_14") (pintype "power_in"))
      (node (ref "U35") (pin "18") (pinfunction "VCC_18") (pintype "power_in"))
      (node (ref "U35") (pin "24") (pinfunction "VCC_24") (pintype "power_in"))
      (node (ref "U35") (pin "34") (pinfunction "VCC_34") (pintype "power_in"))
      (node (ref "U35") (pin "39") (pinfunction "VCC_39") (pintype "power_in"))
      (node (ref "U35") (pin "50") (pinfunction "VCC_50") (pintype "power_in"))
      (node (ref "U35") (pin "6") (pinfunction "VCC_6") (pintype "power_in"))
      (node (ref "U43") (pin "19") (pinfunction "VCCO_6_19") (pintype "power_in"))
      (node (ref "U43") (pin "24") (pinfunction "M1_24") (pintype "input"))
      (node (ref "U43") (pin "25") (pinfunction "M0_25") (pintype "input"))
      (node (ref "U43") (pin "26") (pinfunction "M2_26") (pintype "input"))
      (node (ref "U43") (pin "31") (pinfunction "VCCO_5_31") (pintype "power_in"))
      (node (ref "U43") (pin "46") (pinfunction "VCCO_4_46") (pintype "power_in"))
      (node (ref "U43") (pin "57") (pinfunction "VCCO_3_57") (pintype "power_in"))
      (node (ref "U43") (pin "6") (pinfunction "VCCO_7_6") (pintype "power_in"))
      (node (ref "U43") (pin "70") (pinfunction "VCCO_2_70") (pintype "power_in"))
      (node (ref "U43") (pin "83") (pinfunction "VCCO_1_83") (pintype "power_in"))
      (node (ref "U43") (pin "94") (pinfunction "VCCO_0_94") (pintype "power_in"))
    )
    (net (code "81") (name "unconnected-(C86-VCC-Pad1)") (class "Default")
      (node (ref "C86") (pin "1") (pinfunction "VCC_1") (pintype "passive"))
    )
    (net (code "82") (name "unconnected-(U35-AGND-Pad13)") (class "Default")
      (node (ref "U35") (pin "13") (pinfunction "AGND_13") (pintype "power_in"))
    )
    (net (code "83") (name "unconnected-(U35-AVCC-Pad10)") (class "Default")
      (node (ref "U35") (pin "10") (pinfunction "AVCC_10") (pintype "power_in"))
    )
    (net (code "84") (name "unconnected-(U35-CLKOUT-Pad5)") (class "Default")
      (node (ref "U35") (pin "5") (pinfunction "CLKOUT_5") (pintype "output"))
    )
    (net (code "85") (name "unconnected-(U35-CTL2-Pad38)") (class "Default")
      (node (ref "U35") (pin "38") (pinfunction "CTL2_38") (pintype "output"))
    )
    (net (code "86") (name "unconnected-(U35-PA2-Pad42)") (class "Default")
      (node (ref "U35") (pin "42") (pinfunction "PA2_42") (pintype "bidirectional"))
    )
    (net (code "87") (name "unconnected-(U35-PA3-Pad43)") (class "Default")
      (node (ref "U35") (pin "43") (pinfunction "PA3_43") (pintype "bidirectional"))
    )
    (net (code "88") (name "unconnected-(U35-PA4-Pad44)") (class "Default")
      (node (ref "U35") (pin "44") (pinfunction "PA4_44") (pintype "bidirectional"))
    )
    (net (code "89") (name "unconnected-(U35-PA5-Pad45)") (class "Default")
      (node (ref "U35") (pin "45") (pinfunction "PA5_45") (pintype "bidirectional"))
    )
    (net (code "90") (name "unconnected-(U35-PA6-Pad46)") (class "Default")
      (node (ref "U35") (pin "46") (pinfunction "PA6_46") (pintype "bidirectional"))
    )
    (net (code "91") (name "unconnected-(U35-PA7-Pad47)") (class "Default")
      (node (ref "U35") (pin "47") (pinfunction "PA7_47") (pintype "bidirectional"))
    )
    (net (code "92") (name "unconnected-(U35-~{WAKEUP}-Pad51)") (class "Default")
      (node (ref "U35") (pin "51") (pinfunction "~{WAKEUP}_51") (pintype "input"))
    )
    (net (code "93") (name "unconnected-(U43B-HSWAP_EN-Pad98)") (class "Default")
      (node (ref "U43") (pin "98") (pinfunction "HSWAP_EN_98") (pintype "input"))
    )
    (net (code "94") (name "unconnected-(U43B-TCK-Pad77)") (class "Default")
      (node (ref "U43") (pin "77") (pinfunction "TCK_77") (pintype "bidirectional"))
    )
    (net (code "95") (name "unconnected-(U43B-TDI-Pad100)") (class "Default")
      (node (ref "U43") (pin "100") (pinfunction "TDI_100") (pintype "bidirectional"))
    )
    (net (code "96") (name "unconnected-(U43B-TDO-Pad76)") (class "Default")
      (node (ref "U43") (pin "76") (pinfunction "TDO_76") (pintype "bidirectional"))
    )
    (net (code "97") (name "unconnected-(U43B-TMS-Pad78)") (class "Default")
      (node (ref "U43") (pin "78") (pinfunction "TMS_78") (pintype "bidirectional"))
    )
  )
)
